# Sheet1.net
KiCad netlist of a schematic drawn in Altium Designer
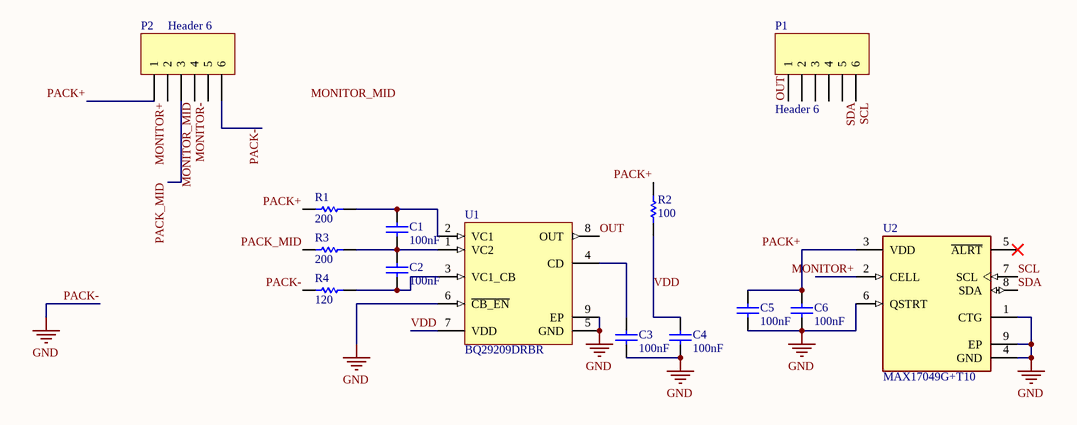
[diagram p0: Sheet1.SchDoc]

(export (version "E")
  (design (tool "Eeschema 10.0.6"))
  (components
    (comp (ref "C1")
      (value "GRM21BR71H104KA01L")
      (footprint "CAPC2013X135X45ML10T25")
      (description "Chip Capacitor, 0.1 uF, +/- 10%, 50 V, -55 to 125 degC, 0805 (2012 Metric), RoHS, Tape and Reel")
      (fields
        (field (name "VOLTAGE") "50V")
        (field (name "CAPACITANCE") "100nF")
        (field (name "TOLERANCE") "10%")
      )
      (libsource (lib "Altium Content Vault") (part "CAP-NP-2"))
    )
    (comp (ref "C2")
      (value "GRM21BR71H104KA01L")
      (footprint "CAPC2013X135X45ML10T25")
      (description "Chip Capacitor, 0.1 uF, +/- 10%, 50 V, -55 to 125 degC, 0805 (2012 Metric), RoHS, Tape and Reel")
      (fields
        (field (name "VOLTAGE") "50V")
        (field (name "CAPACITANCE") "100nF")
        (field (name "TOLERANCE") "10%")
      )
      (libsource (lib "Altium Content Vault") (part "CAP-NP-2"))
    )
    (comp (ref "C3")
      (value "GRM21BR71H104KA01L")
      (footprint "CAPC2013X135X45ML10T25")
      (description "Chip Capacitor, 0.1 uF, +/- 10%, 50 V, -55 to 125 degC, 0805 (2012 Metric), RoHS, Tape and Reel")
      (fields
        (field (name "VOLTAGE") "50V")
        (field (name "CAPACITANCE") "100nF")
        (field (name "TOLERANCE") "10%")
      )
      (libsource (lib "Altium Content Vault") (part "CAP-NP-2"))
    )
    (comp (ref "C4")
      (value "GRM21BR71H104KA01L")
      (footprint "CAPC2013X135X45ML10T25")
      (description "Chip Capacitor, 0.1 uF, +/- 10%, 50 V, -55 to 125 degC, 0805 (2012 Metric), RoHS, Tape and Reel")
      (fields
        (field (name "VOLTAGE") "50V")
        (field (name "CAPACITANCE") "100nF")
        (field (name "TOLERANCE") "10%")
      )
      (libsource (lib "Altium Content Vault") (part "CAP-NP-2"))
    )
    (comp (ref "C5")
      (value "GRM21BR71H104KA01L")
      (footprint "CAPC2013X135X45ML10T25")
      (description "Chip Capacitor, 0.1 uF, +/- 10%, 50 V, -55 to 125 degC, 0805 (2012 Metric), RoHS, Tape and Reel")
      (fields
        (field (name "VOLTAGE") "50V")
        (field (name "CAPACITANCE") "100nF")
        (field (name "TOLERANCE") "10%")
      )
      (libsource (lib "Altium Content Vault") (part "CAP-NP-2"))
    )
    (comp (ref "C6")
      (value "GRM21BR71H104KA01L")
      (footprint "CAPC2013X135X45ML10T25")
      (description "Chip Capacitor, 0.1 uF, +/- 10%, 50 V, -55 to 125 degC, 0805 (2012 Metric), RoHS, Tape and Reel")
      (fields
        (field (name "VOLTAGE") "50V")
        (field (name "CAPACITANCE") "100nF")
        (field (name "TOLERANCE") "10%")
      )
      (libsource (lib "Altium Content Vault") (part "CAP-NP-2"))
    )
    (comp (ref "P1")
      (value "Header 6")
      (footprint "HDR1X6")
      (description "Header, 6-Pin")
      (fields (field (name "PUBLISHER") "Altium Limited"))
      (libsource (lib "Miscellaneous Connectors") (part "Header 6"))
    )
    (comp (ref "P2")
      (value "Header 6")
      (footprint "HDR1X6")
      (description "Header, 6-Pin")
      (fields (field (name "PUBLISHER") "Altium Limited"))
      (libsource (lib "Miscellaneous Connectors") (part "Header 6"))
    )
    (comp (ref "R1")
      (value "CRCW0805200RJNEA")
      (footprint "RESC2013X50X30ML20T20")
      (fields (field (name "MANUFACTURER") "Vishay Dale") (field (name "R") "200"))
      (libsource (lib "Altium Content Vault") (part "RES"))
    )
    (comp (ref "R2")
      (value "CRCW0805100RFKEA")
      (footprint "RESC2013X50X30NL20T20")
      (fields (field (name "MANUFACTURER") "Vishay Dale") (field (name "R") "100"))
      (libsource (lib "Altium Content Vault") (part "RES"))
    )
    (comp (ref "R3")
      (value "CRCW0805200RJNEA")
      (footprint "RESC2013X50X30ML20T20")
      (fields (field (name "MANUFACTURER") "Vishay Dale") (field (name "R") "200"))
      (libsource (lib "Altium Content Vault") (part "RES"))
    )
    (comp (ref "R4")
      (value "ERJ-6ENF1200V")
      (footprint "RESC2013X70X40NL20T20")
      (description "Chip Resistor, 120 Ohm, +/- 1%, 0.125 W, -55 to 155 degC, 0805 (2012 Metric), RoHS, Tape and Reel")
      (fields (field (name "MANUFACTURER") "Panasonic") (field (name "R") "120"))
      (libsource (lib "Altium Content Vault") (part "RES-2"))
    )
    (comp (ref "U1")
      (value "BQ29209DRBR")
      (footprint "DRB0008B_V")
      (fields (field (name "MANUFACTURER") "Texas Instruments"))
      (libsource (lib "Altium Content Vault") (part "TI-BQ29209DRB8-2400X1650TP"))
    )
    (comp (ref "U2")
      (value "MAX17049G+T10")
      (footprint "FP-T822-3-MFG")
      (description "IC FUEL GAUGE LI-ION 2CELL 8TDFN")
      (fields
        (field (name "OCTOPART") "https://octopart.com/max17049g%2Bt10-maxim+integrated-20327626")
        (field (name "MANUFACTURER") "Maxim Integrated")
      )
      (libsource (lib "Altium Content Vault") (part "cecd4ec0661fcbbbb645a1e3250a3e0"))
    )
  )
  (nets
    (net (code "1") (name "/MONITOR+") (class "Default")
      (node (ref "P2") (pin "2") (pinfunction "2_2") (pintype "passive"))
      (node (ref "U2") (pin "2") (pinfunction "CELL_2") (pintype "input"))
    )
    (net (code "2") (name "/MONITOR-") (class "Default")
      (node (ref "P2") (pin "5") (pinfunction "5_5") (pintype "passive"))
    )
    (net (code "3") (name "/MONITOR_MID") (class "Default")
      (node (ref "P2") (pin "4") (pinfunction "4_4") (pintype "passive"))
    )
    (net (code "4") (name "/OUT") (class "Default")
      (node (ref "P1") (pin "1") (pinfunction "1_1") (pintype "passive"))
      (node (ref "U1") (pin "8") (pinfunction "OUT_8") (pintype "output"))
    )
    (net (code "5") (name "/PACK+") (class "Default")
      (node (ref "C5") (pin "1") (pinfunction "1_1") (pintype "passive"))
      (node (ref "C6") (pin "2") (pinfunction "2_2") (pintype "passive"))
      (node (ref "P2") (pin "1") (pinfunction "1_1") (pintype "passive"))
      (node (ref "R1") (pin "1") (pinfunction "1_1") (pintype "passive"))
      (node (ref "R2") (pin "2") (pinfunction "2_2") (pintype "passive"))
      (node (ref "U2") (pin "3") (pinfunction "VDD_3") (pintype "power_in"))
    )
    (net (code "6") (name "/PACK_MID") (class "Default")
      (node (ref "P2") (pin "3") (pinfunction "3_3") (pintype "passive"))
      (node (ref "R3") (pin "1") (pinfunction "1_1") (pintype "passive"))
    )
    (net (code "7") (name "/SCL") (class "Default")
      (node (ref "P1") (pin "6") (pinfunction "6_6") (pintype "passive"))
      (node (ref "U2") (pin "7") (pinfunction "SCL_7") (pintype "input"))
    )
    (net (code "8") (name "/SDA") (class "Default")
      (node (ref "P1") (pin "5") (pinfunction "5_5") (pintype "passive"))
      (node (ref "U2") (pin "8") (pinfunction "SDA_8") (pintype "bidirectional"))
    )
    (net (code "9") (name "/VDD") (class "Default")
      (node (ref "C4") (pin "2") (pinfunction "2_2") (pintype "passive"))
      (node (ref "R2") (pin "1") (pinfunction "1_1") (pintype "passive"))
      (node (ref "U1") (pin "7") (pinfunction "VDD_7") (pintype "power_in"))
    )
    (net (code "10") (name "GND") (class "Default")
      (node (ref "C3") (pin "1") (pinfunction "1_1") (pintype "passive"))
      (node (ref "C4") (pin "1") (pinfunction "1_1") (pintype "passive"))
      (node (ref "C5") (pin "2") (pinfunction "2_2") (pintype "passive"))
      (node (ref "C6") (pin "1") (pinfunction "1_1") (pintype "passive"))
      (node (ref "P2") (pin "6") (pinfunction "6_6") (pintype "passive"))
      (node (ref "R4") (pin "1") (pinfunction "1_1") (pintype "passive"))
      (node (ref "U1") (pin "5") (pinfunction "GND_5") (pintype "power_in"))
      (node (ref "U1") (pin "6") (pinfunction "~{CB_EN}_6") (pintype "input"))
      (node (ref "U1") (pin "9") (pinfunction "EP_9") (pintype "passive"))
      (node (ref "U2") (pin "1") (pinfunction "CTG_1") (pintype "power_in"))
      (node (ref "U2") (pin "4") (pinfunction "GND_4") (pintype "power_in"))
      (node (ref "U2") (pin "6") (pinfunction "QSTRT_6") (pintype "input"))
      (node (ref "U2") (pin "9") (pinfunction "EP_9") (pintype "power_in"))
    )
    (net (code "11") (name "Net-(U1-CD)") (class "Default")
      (node (ref "C3") (pin "2") (pinfunction "2_2") (pintype "passive"))
      (node (ref "U1") (pin "4") (pinfunction "CD_4") (pintype "passive"))
    )
    (net (code "12") (name "Net-(U1-VC1)") (class "Default")
      (node (ref "C1") (pin "2") (pinfunction "2_2") (pintype "passive"))
      (node (ref "R1") (pin "2") (pinfunction "2_2") (pintype "passive"))
      (node (ref "U1") (pin "2") (pinfunction "VC1_2") (pintype "input"))
    )
    (net (code "13") (name "Net-(U1-VC1_CB)") (class "Default")
      (node (ref "C2") (pin "1") (pinfunction "1_1") (pintype "passive"))
      (node (ref "R4") (pin "2") (pinfunction "2_2") (pintype "passive"))
      (node (ref "U1") (pin "3") (pinfunction "VC1_CB_3") (pintype "input"))
    )
    (net (code "14") (name "Net-(U1-VC2)") (class "Default")
      (node (ref "C1") (pin "1") (pinfunction "1_1") (pintype "passive"))
      (node (ref "C2") (pin "2") (pinfunction "2_2") (pintype "passive"))
      (node (ref "R3") (pin "2") (pinfunction "2_2") (pintype "passive"))
      (node (ref "U1") (pin "1") (pinfunction "VC2_1") (pintype "input"))
    )
    (net (code "15") (name "unconnected-(P1-Pad2)") (class "Default")
      (node (ref "P1") (pin "2") (pinfunction "2_2") (pintype "passive"))
    )
    (net (code "16") (name "unconnected-(P1-Pad3)") (class "Default")
      (node (ref "P1") (pin "3") (pinfunction "3_3") (pintype "passive"))
    )
    (net (code "17") (name "unconnected-(P1-Pad4)") (class "Default")
      (node (ref "P1") (pin "4") (pinfunction "4_4") (pintype "passive"))
    )
    (net (code "18") (name "unconnected-(U2-~{ALRT}-Pad5)") (class "Default")
      (node (ref "U2") (pin "5") (pinfunction "~{ALRT}_5") (pintype "open_collector+no_connect"))
    )
  )
)
